# 04_Switch.net
KiCad netlist of a schematic drawn in Altium Designer
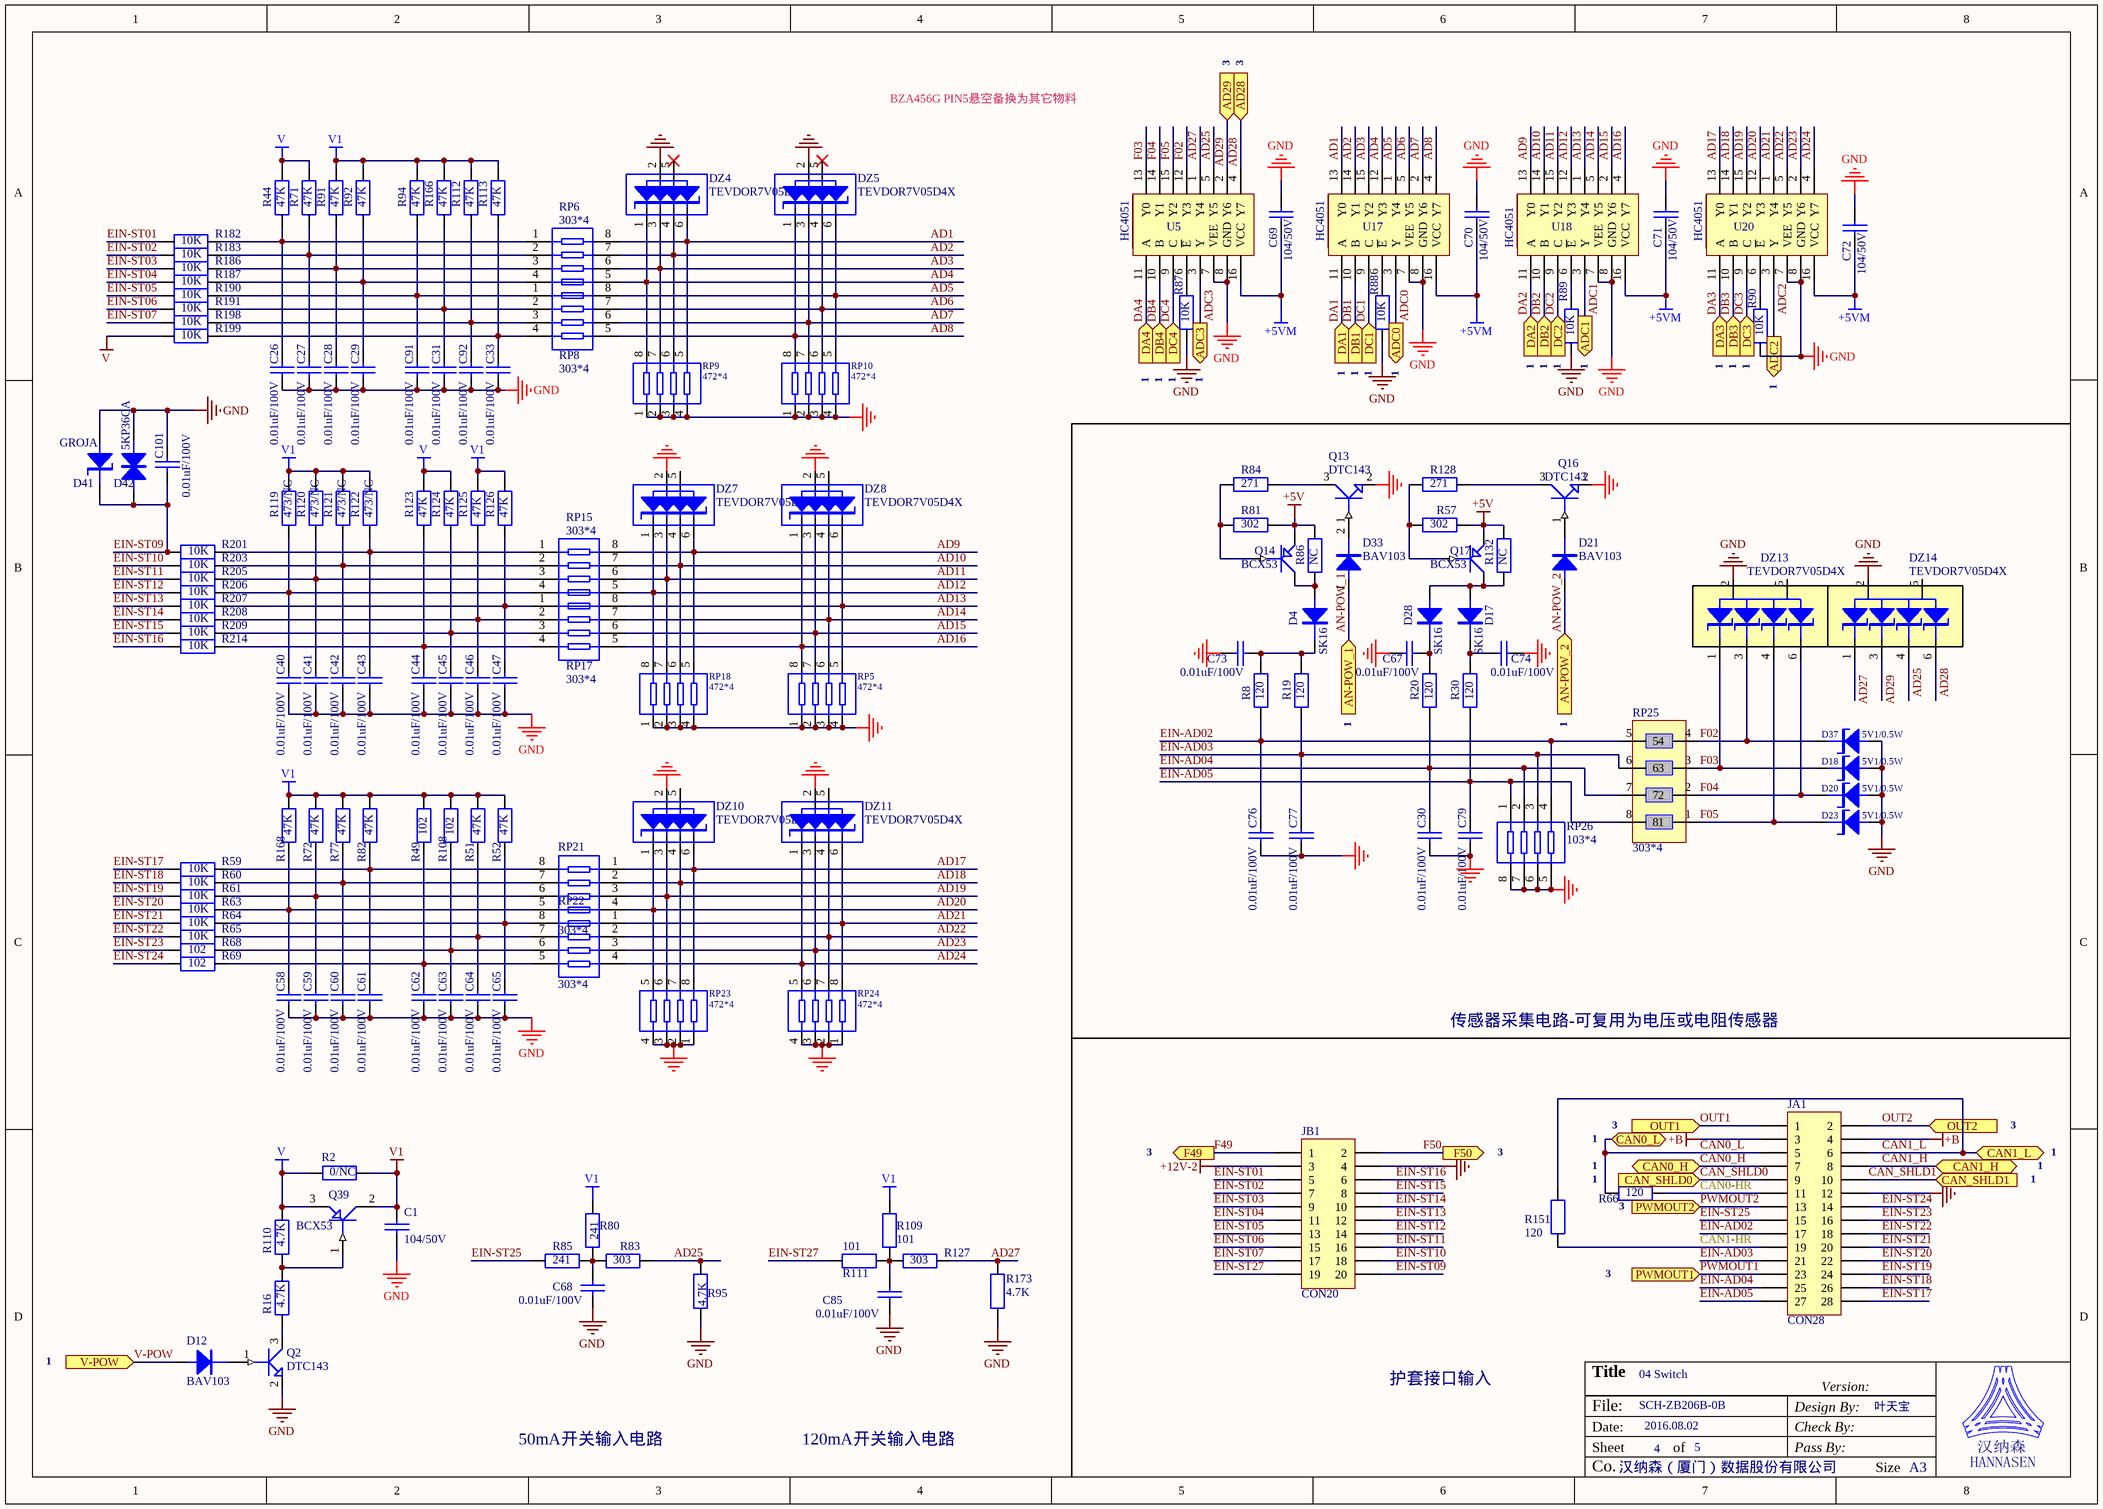
[diagram p0: 04 Switch.SchDoc]

(export (version "E")
  (design (tool "Eeschema 10.0.6"))
  (components
    (comp (ref "C1")
      (value "104/50V")
      (footprint "CR0805")
      (description "贴片电容")
      (libsource (lib "*") (part "CAP"))
    )
    (comp (ref "C26")
      (value "0.01uF/100V")
      (footprint "CR0805")
      (description "Capacitor")
      (libsource (lib "*") (part "CAP"))
    )
    (comp (ref "C27")
      (value "0.01uF/100V")
      (footprint "CR0805")
      (description "Capacitor")
      (libsource (lib "*") (part "CAP"))
    )
    (comp (ref "C28")
      (value "0.01uF/100V")
      (footprint "CR0805")
      (description "Capacitor")
      (libsource (lib "*") (part "CAP"))
    )
    (comp (ref "C29")
      (value "0.01uF/100V")
      (footprint "CR0805")
      (description "Capacitor")
      (libsource (lib "*") (part "CAP"))
    )
    (comp (ref "C30")
      (value "0.01uF/100V")
      (footprint "CR0805")
      (description "Capacitor")
      (libsource (lib "*") (part "CAP"))
    )
    (comp (ref "C31")
      (value "0.01uF/100V")
      (footprint "CR0805")
      (description "Capacitor")
      (libsource (lib "*") (part "CAP"))
    )
    (comp (ref "C33")
      (value "0.01uF/100V")
      (footprint "CR0805")
      (description "Capacitor")
      (libsource (lib "*") (part "CAP"))
    )
    (comp (ref "C40")
      (value "0.01uF/100V")
      (footprint "CR0805")
      (description "Capacitor")
      (libsource (lib "*") (part "CAP"))
    )
    (comp (ref "C41")
      (value "0.01uF/100V")
      (footprint "CR0805")
      (description "Capacitor")
      (libsource (lib "*") (part "CAP"))
    )
    (comp (ref "C42")
      (value "0.01uF/100V")
      (footprint "CR0805")
      (description "Capacitor")
      (libsource (lib "*") (part "CAP"))
    )
    (comp (ref "C43")
      (value "0.01uF/100V")
      (footprint "CR0805")
      (description "Capacitor")
      (libsource (lib "*") (part "CAP"))
    )
    (comp (ref "C44")
      (value "0.01uF/100V")
      (footprint "CR0805")
      (description "Capacitor")
      (libsource (lib "*") (part "CAP"))
    )
    (comp (ref "C45")
      (value "0.01uF/100V")
      (footprint "CR0805")
      (description "Capacitor")
      (libsource (lib "*") (part "CAP"))
    )
    (comp (ref "C46")
      (value "0.01uF/100V")
      (footprint "CR0805")
      (description "Capacitor")
      (libsource (lib "*") (part "CAP"))
    )
    (comp (ref "C47")
      (value "0.01uF/100V")
      (footprint "CR0805")
      (description "Capacitor")
      (libsource (lib "*") (part "CAP"))
    )
    (comp (ref "C58")
      (value "0.01uF/100V")
      (footprint "CR0805")
      (description "Capacitor")
      (libsource (lib "*") (part "CAP"))
    )
    (comp (ref "C59")
      (value "0.01uF/100V")
      (footprint "CR0805")
      (description "Capacitor")
      (libsource (lib "*") (part "CAP"))
    )
    (comp (ref "C60")
      (value "0.01uF/100V")
      (footprint "CR0805")
      (description "Capacitor")
      (libsource (lib "*") (part "CAP"))
    )
    (comp (ref "C61")
      (value "0.01uF/100V")
      (footprint "CR0805")
      (description "Capacitor")
      (libsource (lib "*") (part "CAP"))
    )
    (comp (ref "C62")
      (value "0.01uF/100V")
      (footprint "CR0805")
      (description "Capacitor")
      (libsource (lib "*") (part "CAP"))
    )
    (comp (ref "C63")
      (value "0.01uF/100V")
      (footprint "CR0805")
      (description "Capacitor")
      (libsource (lib "*") (part "CAP"))
    )
    (comp (ref "C64")
      (value "0.01uF/100V")
      (footprint "CR0805")
      (description "Capacitor")
      (libsource (lib "*") (part "CAP"))
    )
    (comp (ref "C65")
      (value "0.01uF/100V")
      (footprint "CR0805")
      (description "Capacitor")
      (libsource (lib "*") (part "CAP"))
    )
    (comp (ref "C67")
      (value "0.01uF/100V")
      (footprint "CR0805")
      (description "Capacitor")
      (libsource (lib "*") (part "CAP"))
    )
    (comp (ref "C68")
      (value "0.01uF/100V")
      (footprint "CR0805")
      (description "Capacitor")
      (libsource (lib "*") (part "CAP"))
    )
    (comp (ref "C69")
      (value "104/50V")
      (footprint "CR0805")
      (description "Capacitor")
      (libsource (lib "*") (part "CAP"))
    )
    (comp (ref "C70")
      (value "104/50V")
      (footprint "CR0805")
      (description "Capacitor")
      (libsource (lib "*") (part "CAP"))
    )
    (comp (ref "C71")
      (value "104/50V")
      (footprint "CR0805")
      (description "Capacitor")
      (libsource (lib "*") (part "CAP"))
    )
    (comp (ref "C72")
      (value "104/50V")
      (footprint "CR0805")
      (description "Capacitor")
      (libsource (lib "*") (part "CAP"))
    )
    (comp (ref "C73")
      (value "0.01uF/100V")
      (footprint "CR0805")
      (description "Capacitor")
      (libsource (lib "*") (part "CAP"))
    )
    (comp (ref "C74")
      (value "0.01uF/100V")
      (footprint "CR0805")
      (description "Capacitor")
      (libsource (lib "*") (part "CAP"))
    )
    (comp (ref "C76")
      (value "0.01uF/100V")
      (footprint "CR0805")
      (description "Capacitor")
      (libsource (lib "*") (part "CAP"))
    )
    (comp (ref "C77")
      (value "0.01uF/100V")
      (footprint "CR0805")
      (description "Capacitor")
      (libsource (lib "*") (part "CAP"))
    )
    (comp (ref "C79")
      (value "0.01uF/100V")
      (footprint "CR0805")
      (description "Capacitor")
      (libsource (lib "*") (part "CAP"))
    )
    (comp (ref "C85")
      (value "0.01uF/100V")
      (footprint "CR0805")
      (description "Capacitor")
      (libsource (lib "*") (part "CAP"))
    )
    (comp (ref "C91")
      (value "0.01uF/100V")
      (footprint "CR0805")
      (description "Capacitor")
      (libsource (lib "*") (part "CAP"))
    )
    (comp (ref "C92")
      (value "0.01uF/100V")
      (footprint "CR0805")
      (description "Capacitor")
      (libsource (lib "*") (part "CAP"))
    )
    (comp (ref "C101")
      (value "0.01uF/100V")
      (footprint "CR0805")
      (description "Capacitor")
      (libsource (lib "*") (part "CAP"))
    )
    (comp (ref "D4")
      (value "SK16")
      (footprint "SMA")
      (description "二极管")
      (libsource (lib "*") (part "DIODE"))
    )
    (comp (ref "D12")
      (value "BAV103")
      (footprint "SOD-80C")
      (description "二极管")
      (libsource (lib "*") (part "DIODE"))
    )
    (comp (ref "D17")
      (value "SK16")
      (footprint "SMA")
      (description "二极管")
      (libsource (lib "*") (part "DIODE"))
    )
    (comp (ref "D18")
      (value "5V1/0.5W")
      (footprint "SOD-80C")
      (description "稳压二极管")
      (libsource (lib "*") (part "DW"))
    )
    (comp (ref "D20")
      (value "5V1/0.5W")
      (footprint "SOD-80C")
      (description "稳压二极管")
      (libsource (lib "*") (part "DW"))
    )
    (comp (ref "D21")
      (value "BAV103")
      (footprint "SOD-80C")
      (description "二极管")
      (libsource (lib "*") (part "DIODE"))
    )
    (comp (ref "D23")
      (value "5V1/0.5W")
      (footprint "SOD-80C")
      (description "稳压二极管")
      (libsource (lib "*") (part "DW"))
    )
    (comp (ref "D28")
      (value "SK16")
      (footprint "SMA")
      (description "二极管")
      (libsource (lib "*") (part "DIODE"))
    )
    (comp (ref "D33")
      (value "BAV103")
      (footprint "SOD-80C")
      (description "二极管")
      (libsource (lib "") (part "DIODE_1"))
    )
    (comp (ref "D37")
      (value "5V1/0.5W")
      (footprint "SOD-80C")
      (description "稳压二极管")
      (libsource (lib "*") (part "DW"))
    )
    (comp (ref "D41")
      (value "GROJA")
      (footprint "SMA")
      (description "稳压二极管")
      (libsource (lib "*") (part "DW"))
    )
    (comp (ref "D42") (value "5KP36CA") (footprint "SMB-D") (libsource (lib "*") (part "TVS")))
    (comp (ref "DZ4")
      (value "TEVDOR7V05D4X")
      (footprint "SOT-457")
      (description "二极管排")
      (libsource (lib "yibiaoschlib") (part "TEVDOR7V05D4X"))
    )
    (comp (ref "DZ5")
      (value "TEVDOR7V05D4X")
      (footprint "SOT-457")
      (description "二极管排")
      (libsource (lib "yibiaoschlib") (part "TEVDOR7V05D4X"))
    )
    (comp (ref "DZ7")
      (value "TEVDOR7V05D4X")
      (footprint "SOT-457")
      (description "二极管排")
      (libsource (lib "yibiaoschlib") (part "TEVDOR7V05D4X"))
    )
    (comp (ref "DZ8")
      (value "TEVDOR7V05D4X")
      (footprint "SOT-457")
      (description "二极管排")
      (libsource (lib "yibiaoschlib") (part "TEVDOR7V05D4X"))
    )
    (comp (ref "DZ10")
      (value "TEVDOR7V05D4X")
      (footprint "SOT-457")
      (description "二极管排")
      (libsource (lib "yibiaoschlib") (part "TEVDOR7V05D4X"))
    )
    (comp (ref "DZ11")
      (value "TEVDOR7V05D4X")
      (footprint "SOT-457")
      (description "二极管排")
      (libsource (lib "yibiaoschlib") (part "TEVDOR7V05D4X"))
    )
    (comp (ref "DZ13")
      (value "TEVDOR7V05D4X")
      (footprint "SOT-457")
      (description "二极管排")
      (libsource (lib "*") (part "TEVDOR7V05D4X"))
    )
    (comp (ref "DZ14")
      (value "TEVDOR7V05D4X")
      (footprint "SOT-457")
      (description "二极管排")
      (libsource (lib "*") (part "TEVDOR7V05D4X"))
    )
    (comp (ref "JA1") (value "CON28") (footprint "AMP DIP28") (libsource (lib "YDM-SQ-1SCH") (part "CON28")))
    (comp (ref "JB1") (value "CON20") (footprint "AMP DIP20") (libsource (lib "YDM-SQ-1SCH") (part "CON20")))
    (comp (ref "Q2")
      (value "DTC143")
      (footprint "SOT23")
      (description "NPN")
      (libsource (lib "Ô­ÀíÍ¼¿â-1SCH") (part "DTC143"))
    )
    (comp (ref "Q13")
      (value "DTC143")
      (footprint "SOT23")
      (description "NPN")
      (libsource (lib "Ô­ÀíÍ¼¿â-1SCH") (part "DTC143"))
    )
    (comp (ref "Q14")
      (value "BCX53")
      (footprint "SOT89")
      (description "贴片三极管")
      (libsource (lib "*") (part "PNP1"))
    )
    (comp (ref "Q16")
      (value "DTC143")
      (footprint "SOT23")
      (description "NPN")
      (libsource (lib "Ô­ÀíÍ¼¿â-1SCH") (part "DTC143"))
    )
    (comp (ref "Q17")
      (value "BCX53")
      (footprint "SOT89")
      (description "贴片三极管")
      (libsource (lib "*") (part "PNP1"))
    )
    (comp (ref "Q39")
      (value "BCX53")
      (footprint "SOT89")
      (description "PNP三极管")
      (libsource (lib "Ô­ÀíÍ¼¿â-1SCH") (part "BSP631"))
    )
    (comp (ref "R2")
      (value "0/NC")
      (footprint "CR1206")
      (description "贴片电阻")
      (libsource (lib "YDM-SQ-1SCH") (part "RES"))
    )
    (comp (ref "R8")
      (value "120")
      (footprint "CR1206")
      (description "贴片电阻")
      (libsource (lib "*") (part "RES"))
    )
    (comp (ref "R16")
      (value "4.7K")
      (footprint "CR1206")
      (description "贴片电阻")
      (libsource (lib "*") (part "RES"))
    )
    (comp (ref "R19")
      (value "120")
      (footprint "CR1206")
      (description "贴片电阻")
      (libsource (lib "*") (part "RES"))
    )
    (comp (ref "R20")
      (value "120")
      (footprint "CR1206")
      (description "贴片电阻")
      (libsource (lib "*") (part "RES"))
    )
    (comp (ref "R30")
      (value "120")
      (footprint "CR1206")
      (description "贴片电阻")
      (libsource (lib "*") (part "RES"))
    )
    (comp (ref "R44")
      (value "47K")
      (footprint "CR0805")
      (description "贴片电阻")
      (libsource (lib "*") (part "RES"))
    )
    (comp (ref "R49")
      (value "102")
      (footprint "CR2010")
      (description "贴片电阻")
      (libsource (lib "*") (part "RES"))
    )
    (comp (ref "R51")
      (value "47K")
      (footprint "CR0805")
      (description "贴片电阻")
      (libsource (lib "*") (part "RES"))
    )
    (comp (ref "R52")
      (value "47K")
      (footprint "CR0805")
      (description "贴片电阻")
      (libsource (lib "*") (part "RES"))
    )
    (comp (ref "R57")
      (value "302")
      (footprint "CR0805")
      (description "贴片电阻")
      (libsource (lib "*") (part "RES"))
    )
    (comp (ref "R59")
      (value "10K")
      (footprint "CR1206")
      (description "贴片电阻")
      (libsource (lib "*") (part "RES"))
    )
    (comp (ref "R60")
      (value "10K")
      (footprint "CR1206")
      (description "贴片电阻")
      (libsource (lib "*") (part "RES"))
    )
    (comp (ref "R61")
      (value "10K")
      (footprint "CR1206")
      (description "贴片电阻")
      (libsource (lib "*") (part "RES"))
    )
    (comp (ref "R63")
      (value "10K")
      (footprint "CR1206")
      (description "贴片电阻")
      (libsource (lib "*") (part "RES"))
    )
    (comp (ref "R64")
      (value "10K")
      (footprint "CR1206")
      (description "贴片电阻")
      (libsource (lib "*") (part "RES"))
    )
    (comp (ref "R65")
      (value "10K")
      (footprint "CR1206")
      (description "贴片电阻")
      (libsource (lib "*") (part "RES"))
    )
    (comp (ref "R66")
      (value "120")
      (footprint "CR0805")
      (description "贴片电阻")
      (libsource (lib "*") (part "RES"))
    )
    (comp (ref "R68")
      (value "102")
      (footprint "CR2010")
      (description "贴片电阻")
      (libsource (lib "*") (part "RES"))
    )
    (comp (ref "R69")
      (value "102")
      (footprint "CR2010")
      (description "贴片电阻")
      (libsource (lib "*") (part "RES"))
    )
    (comp (ref "R71")
      (value "47K")
      (footprint "CR0805")
      (description "贴片电阻")
      (libsource (lib "*") (part "RES"))
    )
    (comp (ref "R72")
      (value "47K")
      (footprint "CR0805")
      (description "贴片电阻")
      (libsource (lib "*") (part "RES"))
    )
    (comp (ref "R77")
      (value "47K")
      (footprint "CR0805")
      (description "贴片电阻")
      (libsource (lib "*") (part "RES"))
    )
    (comp (ref "R80")
      (value "241")
      (footprint "R-3W")
      (description "贴片电阻")
      (libsource (lib "*") (part "RES"))
    )
    (comp (ref "R81")
      (value "302")
      (footprint "CR0805")
      (description "贴片电阻")
      (libsource (lib "*") (part "RES"))
    )
    (comp (ref "R82")
      (value "47K")
      (footprint "CR0805")
      (description "贴片电阻")
      (libsource (lib "*") (part "RES"))
    )
    (comp (ref "R83")
      (value "303")
      (footprint "CR0805")
      (description "贴片电阻")
      (libsource (lib "*") (part "RES"))
    )
    (comp (ref "R84")
      (value "271")
      (footprint "CR0805")
      (description "贴片电阻")
      (libsource (lib "*") (part "RES"))
    )
    (comp (ref "R85")
      (value "241")
      (footprint "R-3W")
      (description "贴片电阻")
      (libsource (lib "*") (part "RES"))
    )
    (comp (ref "R86")
      (value "NC")
      (footprint "CR1206")
      (description "贴片电阻")
      (libsource (lib "*") (part "RES"))
    )
    (comp (ref "R87")
      (value "10K")
      (footprint "CR0805")
      (description "贴片电阻")
      (libsource (lib "*") (part "RES"))
    )
    (comp (ref "R88")
      (value "10K")
      (footprint "CR0805")
      (description "贴片电阻")
      (libsource (lib "*") (part "RES"))
    )
    (comp (ref "R89")
      (value "10K")
      (footprint "CR0805")
      (description "贴片电阻")
      (libsource (lib "*") (part "RES"))
    )
    (comp (ref "R90")
      (value "10K")
      (footprint "CR0805")
      (description "贴片电阻")
      (libsource (lib "*") (part "RES"))
    )
    (comp (ref "R91")
      (value "47K")
      (footprint "CR0805")
      (description "贴片电阻")
      (libsource (lib "*") (part "RES"))
    )
    (comp (ref "R92")
      (value "47K")
      (footprint "CR0805")
      (description "贴片电阻")
      (libsource (lib "*") (part "RES"))
    )
    (comp (ref "R94")
      (value "47K")
      (footprint "CR0805")
      (description "贴片电阻")
      (libsource (lib "*") (part "RES"))
    )
    (comp (ref "R95")
      (value "4.7K")
      (footprint "CR0805")
      (description "贴片电阻")
      (libsource (lib "*") (part "RES"))
    )
    (comp (ref "R108")
      (value "102")
      (footprint "CR2010")
      (description "贴片电阻")
      (libsource (lib "*") (part "RES"))
    )
    (comp (ref "R109")
      (value "101")
      (footprint "R-3W")
      (description "贴片电阻")
      (libsource (lib "*") (part "RES"))
    )
    (comp (ref "R110")
      (value "4.7K")
      (footprint "CR0805")
      (description "贴片电阻")
      (libsource (lib "*") (part "RES"))
    )
    (comp (ref "R111")
      (value "101")
      (footprint "R-3W")
      (description "贴片电阻")
      (libsource (lib "*") (part "RES"))
    )
    (comp (ref "R112")
      (value "47K")
      (footprint "CR0805")
      (description "贴片电阻")
      (libsource (lib "*") (part "RES"))
    )
    (comp (ref "R113")
      (value "47K")
      (footprint "CR0805")
      (description "贴片电阻")
      (libsource (lib "*") (part "RES"))
    )
    (comp (ref "R119")
      (value "473/NC")
      (footprint "CR0805")
      (description "贴片电阻")
      (libsource (lib "*") (part "RES"))
    )
    (comp (ref "R120")
      (value "473/NC")
      (footprint "CR0805")
      (description "贴片电阻")
      (libsource (lib "*") (part "RES"))
    )
    (comp (ref "R121")
      (value "473/NC")
      (footprint "CR0805")
      (description "贴片电阻")
      (libsource (lib "*") (part "RES"))
    )
    (comp (ref "R122")
      (value "473/NC")
      (footprint "CR0805")
      (description "贴片电阻")
      (libsource (lib "*") (part "RES"))
    )
    (comp (ref "R123")
      (value "47K")
      (footprint "CR0805")
      (description "贴片电阻")
      (libsource (lib "*") (part "RES"))
    )
    (comp (ref "R124")
      (value "47K")
      (footprint "CR0805")
      (description "贴片电阻")
      (libsource (lib "*") (part "RES"))
    )
    (comp (ref "R125")
      (value "47K")
      (footprint "CR0805")
      (description "贴片电阻")
      (libsource (lib "*") (part "RES"))
    )
    (comp (ref "R126")
      (value "47K")
      (footprint "CR0805")
      (description "贴片电阻")
      (libsource (lib "*") (part "RES"))
    )
    (comp (ref "R127")
      (value "303")
      (footprint "CR0805")
      (description "贴片电阻")
      (libsource (lib "*") (part "RES"))
    )
    (comp (ref "R128")
      (value "271")
      (footprint "CR0805")
      (description "贴片电阻")
      (libsource (lib "*") (part "RES"))
    )
    (comp (ref "R132")
      (value "NC")
      (footprint "CR1206")
      (description "贴片电阻")
      (libsource (lib "*") (part "RES"))
    )
    (comp (ref "R151")
      (value "120")
      (footprint "CR0805")
      (description "贴片电阻")
      (libsource (lib "*") (part "RES"))
    )
    (comp (ref "R166")
      (value "47K")
      (footprint "CR0805")
      (description "贴片电阻")
      (libsource (lib "*") (part "RES"))
    )
    (comp (ref "R168")
      (value "47K")
      (footprint "CR0805")
      (description "贴片电阻")
      (libsource (lib "*") (part "RES"))
    )
    (comp (ref "R173")
      (value "4.7K")
      (footprint "CR0805")
      (description "贴片电阻")
      (libsource (lib "*") (part "RES"))
    )
    (comp (ref "R182")
      (value "10K")
      (footprint "CR1206")
      (description "贴片电阻")
      (libsource (lib "*") (part "RES"))
    )
    (comp (ref "R183")
      (value "10K")
      (footprint "CR1206")
      (description "贴片电阻")
      (libsource (lib "*") (part "RES"))
    )
    (comp (ref "R186")
      (value "10K")
      (footprint "CR1206")
      (description "贴片电阻")
      (libsource (lib "*") (part "RES"))
    )
    (comp (ref "R187")
      (value "10K")
      (footprint "CR1206")
      (description "贴片电阻")
      (libsource (lib "*") (part "RES"))
    )
    (comp (ref "R190")
      (value "10K")
      (footprint "CR1206")
      (description "贴片电阻")
      (libsource (lib "*") (part "RES"))
    )
    (comp (ref "R191")
      (value "10K")
      (footprint "CR1206")
      (description "贴片电阻")
      (libsource (lib "*") (part "RES"))
    )
    (comp (ref "R198")
      (value "10K")
      (footprint "CR1206")
      (description "贴片电阻")
      (libsource (lib "*") (part "RES"))
    )
    (comp (ref "R199")
      (value "10K")
      (footprint "CR1206")
      (description "贴片电阻")
      (libsource (lib "*") (part "RES"))
    )
    (comp (ref "R201")
      (value "10K")
      (footprint "CR1206")
      (description "贴片电阻")
      (libsource (lib "*") (part "RES"))
    )
    (comp (ref "R203")
      (value "10K")
      (footprint "CR1206")
      (description "贴片电阻")
      (libsource (lib "*") (part "RES"))
    )
    (comp (ref "R205")
      (value "10K")
      (footprint "CR1206")
      (description "贴片电阻")
      (libsource (lib "*") (part "RES"))
    )
    (comp (ref "R206")
      (value "10K")
      (footprint "CR1206")
      (description "贴片电阻")
      (libsource (lib "*") (part "RES"))
    )
    (comp (ref "R207")
      (value "10K")
      (footprint "CR1206")
      (description "贴片电阻")
      (libsource (lib "*") (part "RES"))
    )
    (comp (ref "R208")
      (value "10K")
      (footprint "CR1206")
      (description "贴片电阻")
      (libsource (lib "*") (part "RES"))
    )
    (comp (ref "R209")
      (value "10K")
      (footprint "CR1206")
      (description "贴片电阻")
      (libsource (lib "*") (part "RES"))
    )
    (comp (ref "R214")
      (value "10K")
      (footprint "CR1206")
      (description "贴片电阻")
      (libsource (lib "*") (part "RES"))
    )
    (comp (ref "RP5")
      (value "472*4")
      (footprint "R4")
      (description "排阻")
      (libsource (lib "yibiaoschlib") (part "RN"))
    )
    (comp (ref "RP6")
      (value "303*4")
      (footprint "R4")
      (description "贴片排阻")
      (libsource (lib "*") (part "R_LINE4"))
    )
    (comp (ref "RP8")
      (value "303*4")
      (footprint "R4")
      (description "贴片排阻")
      (libsource (lib "*") (part "R_LINE4"))
    )
    (comp (ref "RP9")
      (value "472*4")
      (footprint "R4")
      (description "排阻")
      (libsource (lib "yibiaoschlib") (part "RN"))
    )
    (comp (ref "RP10")
      (value "472*4")
      (footprint "R4")
      (description "排阻")
      (libsource (lib "yibiaoschlib") (part "RN"))
    )
    (comp (ref "RP15")
      (value "303*4")
      (footprint "R4")
      (description "贴片排阻")
      (libsource (lib "*") (part "R_LINE4"))
    )
    (comp (ref "RP17")
      (value "303*4")
      (footprint "R4")
      (description "贴片排阻")
      (libsource (lib "*") (part "R_LINE4"))
    )
    (comp (ref "RP18")
      (value "472*4")
      (footprint "R4")
      (description "排阻")
      (libsource (lib "yibiaoschlib") (part "RN"))
    )
    (comp (ref "RP21")
      (value "303*4")
      (footprint "R4")
      (description "贴片排阻")
      (libsource (lib "*") (part "R_LINE4"))
    )
    (comp (ref "RP22")
      (value "303*4")
      (footprint "R4")
      (description "贴片排阻")
      (libsource (lib "*") (part "R_LINE4"))
    )
    (comp (ref "RP23")
      (value "472*4")
      (footprint "R4")
      (description "排阻")
      (libsource (lib "yibiaoschlib") (part "RN"))
    )
    (comp (ref "RP24")
      (value "472*4")
      (footprint "R4")
      (description "排阻")
      (libsource (lib "yibiaoschlib") (part "RN"))
    )
    (comp (ref "RP25") (value "303*4") (footprint "R4") (libsource (lib "*") (part "R_ARRAY")))
    (comp (ref "RP26")
      (value "103*4")
      (footprint "R4")
      (description "排阻")
      (libsource (lib "*") (part "R_LINE4"))
    )
    (comp (ref "U5")
      (value "HC4051")
      (footprint "SO-16")
      (description "IC-8路模拟开关集成快")
      (libsource (lib "YDM-SQ-1SCH") (part "HC4051"))
    )
    (comp (ref "U17")
      (value "HC4051")
      (footprint "SO-16")
      (description "IC-8路模拟开关集成快")
      (libsource (lib "YDM-SQ-1SCH") (part "HC4051"))
    )
    (comp (ref "U18")
      (value "HC4051")
      (footprint "SO-16")
      (description "IC-8路模拟开关集成快")
      (libsource (lib "YDM-SQ-1SCH") (part "HC4051"))
    )
    (comp (ref "U20")
      (value "HC4051")
      (footprint "SO-16")
      (description "IC-8路模拟开关集成快")
      (libsource (lib "YDM-SQ-1SCH") (part "HC4051"))
    )
  )
  (nets
    (net (code "1") (name "+5V") (class "Default")
      (node (ref "Q14") (pin "3") (pinfunction "E_3") (pintype "passive"))
      (node (ref "Q17") (pin "3") (pinfunction "E_3") (pintype "passive"))
      (node (ref "R132") (pin "1") (pinfunction "1_1") (pintype "passive"))
      (node (ref "R57") (pin "1") (pinfunction "1_1") (pintype "passive"))
      (node (ref "R81") (pin "1") (pinfunction "1_1") (pintype "passive"))
      (node (ref "R86") (pin "1") (pinfunction "1_1") (pintype "passive"))
    )
    (net (code "2") (name "+5VM") (class "Default")
      (node (ref "C69") (pin "2") (pinfunction "2_2") (pintype "passive"))
      (node (ref "C70") (pin "2") (pinfunction "2_2") (pintype "passive"))
      (node (ref "C71") (pin "2") (pinfunction "2_2") (pintype "passive"))
      (node (ref "C72") (pin "2") (pinfunction "2_2") (pintype "passive"))
      (node (ref "U17") (pin "16") (pinfunction "VCC_16") (pintype "passive"))
      (node (ref "U18") (pin "16") (pinfunction "VCC_16") (pintype "passive"))
      (node (ref "U20") (pin "16") (pinfunction "VCC_16") (pintype "passive"))
      (node (ref "U5") (pin "16") (pinfunction "VCC_16") (pintype "passive"))
    )
    (net (code "3") (name "+12V-2") (class "Default")
      (node (ref "JB1") (pin "3") (pinfunction "3_3") (pintype "passive"))
    )
    (net (code "4") (name "+B") (class "Default")
      (node (ref "JA1") (pin "3") (pinfunction "3_3") (pintype "passive"))
      (node (ref "JA1") (pin "4") (pinfunction "4_4") (pintype "passive"))
    )
    (net (code "5") (name "/AD1") (class "Default")
      (node (ref "DZ4") (pin "6") (pintype "passive"))
      (node (ref "RP6") (pin "8") (pinfunction "8_8") (pintype "passive"))
      (node (ref "RP9") (pin "5") (pinfunction "5_5") (pintype "passive"))
      (node (ref "U17") (pin "13") (pinfunction "Y0_13") (pintype "passive"))
    )
    (net (code "6") (name "/AD2") (class "Default")
      (node (ref "DZ4") (pin "4") (pintype "passive"))
      (node (ref "RP6") (pin "7") (pinfunction "7_7") (pintype "passive"))
      (node (ref "RP9") (pin "6") (pinfunction "6_6") (pintype "passive"))
      (node (ref "U17") (pin "14") (pinfunction "Y1_14") (pintype "passive"))
    )
    (net (code "7") (name "/AD3") (class "Default")
      (node (ref "DZ4") (pin "3") (pintype "passive"))
      (node (ref "RP6") (pin "6") (pinfunction "6_6") (pintype "passive"))
      (node (ref "RP9") (pin "7") (pinfunction "7_7") (pintype "passive"))
      (node (ref "U17") (pin "15") (pinfunction "Y2_15") (pintype "passive"))
    )
    (net (code "8") (name "/AD4") (class "Default")
      (node (ref "DZ4") (pin "1") (pintype "passive"))
      (node (ref "RP6") (pin "5") (pinfunction "5_5") (pintype "passive"))
      (node (ref "RP9") (pin "8") (pinfunction "8_8") (pintype "passive"))
      (node (ref "U17") (pin "12") (pinfunction "Y3_12") (pintype "passive"))
    )
    (net (code "9") (name "/AD5") (class "Default")
      (node (ref "DZ5") (pin "6") (pintype "passive"))
      (node (ref "RP10") (pin "5") (pinfunction "5_5") (pintype "passive"))
      (node (ref "RP8") (pin "8") (pinfunction "8_8") (pintype "passive"))
      (node (ref "U17") (pin "1") (pinfunction "Y4_1") (pintype "passive"))
    )
    (net (code "10") (name "/AD6") (class "Default")
      (node (ref "DZ5") (pin "4") (pintype "passive"))
      (node (ref "RP10") (pin "6") (pinfunction "6_6") (pintype "passive"))
      (node (ref "RP8") (pin "7") (pinfunction "7_7") (pintype "passive"))
      (node (ref "U17") (pin "5") (pinfunction "Y5_5") (pintype "passive"))
    )
    (net (code "11") (name "/AD7") (class "Default")
      (node (ref "DZ5") (pin "3") (pintype "passive"))
      (node (ref "RP10") (pin "7") (pinfunction "7_7") (pintype "passive"))
      (node (ref "RP8") (pin "6") (pinfunction "6_6") (pintype "passive"))
      (node (ref "U17") (pin "2") (pinfunction "Y6_2") (pintype "passive"))
    )
    (net (code "12") (name "/AD8") (class "Default")
      (node (ref "DZ5") (pin "1") (pintype "passive"))
      (node (ref "RP10") (pin "8") (pinfunction "8_8") (pintype "passive"))
      (node (ref "RP8") (pin "5") (pinfunction "5_5") (pintype "passive"))
      (node (ref "U17") (pin "4") (pinfunction "Y7_4") (pintype "passive"))
    )
    (net (code "13") (name "/AD9") (class "Default")
      (node (ref "DZ7") (pin "6") (pintype "passive"))
      (node (ref "RP15") (pin "8") (pinfunction "8_8") (pintype "passive"))
      (node (ref "RP18") (pin "5") (pinfunction "5_5") (pintype "passive"))
      (node (ref "U18") (pin "13") (pinfunction "Y0_13") (pintype "passive"))
    )
    (net (code "14") (name "/AD10") (class "Default")
      (node (ref "DZ7") (pin "4") (pintype "passive"))
      (node (ref "RP15") (pin "7") (pinfunction "7_7") (pintype "passive"))
      (node (ref "RP18") (pin "6") (pinfunction "6_6") (pintype "passive"))
      (node (ref "U18") (pin "14") (pinfunction "Y1_14") (pintype "passive"))
    )
    (net (code "15") (name "/AD11") (class "Default")
      (node (ref "DZ7") (pin "3") (pintype "passive"))
      (node (ref "RP15") (pin "6") (pinfunction "6_6") (pintype "passive"))
      (node (ref "RP18") (pin "7") (pinfunction "7_7") (pintype "passive"))
      (node (ref "U18") (pin "15") (pinfunction "Y2_15") (pintype "passive"))
    )
    (net (code "16") (name "/AD12") (class "Default")
      (node (ref "DZ7") (pin "1") (pintype "passive"))
      (node (ref "RP15") (pin "5") (pinfunction "5_5") (pintype "passive"))
      (node (ref "RP18") (pin "8") (pinfunction "8_8") (pintype "passive"))
      (node (ref "U18") (pin "12") (pinfunction "Y3_12") (pintype "passive"))
    )
    (net (code "17") (name "/AD13") (class "Default")
      (node (ref "DZ8") (pin "6") (pintype "passive"))
      (node (ref "RP17") (pin "8") (pinfunction "8_8") (pintype "passive"))
      (node (ref "RP5") (pin "5") (pinfunction "5_5") (pintype "passive"))
      (node (ref "U18") (pin "1") (pinfunction "Y4_1") (pintype "passive"))
    )
    (net (code "18") (name "/AD14") (class "Default")
      (node (ref "DZ8") (pin "4") (pintype "passive"))
      (node (ref "RP17") (pin "7") (pinfunction "7_7") (pintype "passive"))
      (node (ref "RP5") (pin "6") (pinfunction "6_6") (pintype "passive"))
      (node (ref "U18") (pin "5") (pinfunction "Y5_5") (pintype "passive"))
    )
    (net (code "19") (name "/AD15") (class "Default")
      (node (ref "DZ8") (pin "3") (pintype "passive"))
      (node (ref "RP17") (pin "6") (pinfunction "6_6") (pintype "passive"))
      (node (ref "RP5") (pin "7") (pinfunction "7_7") (pintype "passive"))
      (node (ref "U18") (pin "2") (pinfunction "Y6_2") (pintype "passive"))
    )
    (net (code "20") (name "/AD16") (class "Default")
      (node (ref "DZ8") (pin "1") (pintype "passive"))
      (node (ref "RP17") (pin "5") (pinfunction "5_5") (pintype "passive"))
      (node (ref "RP5") (pin "8") (pinfunction "8_8") (pintype "passive"))
      (node (ref "U18") (pin "4") (pinfunction "Y7_4") (pintype "passive"))
    )
    (net (code "21") (name "/AD17") (class "Default")
      (node (ref "DZ10") (pin "6") (pintype "passive"))
      (node (ref "RP21") (pin "1") (pinfunction "1_1") (pintype "passive"))
      (node (ref "RP23") (pin "8") (pinfunction "8_8") (pintype "passive"))
      (node (ref "U20") (pin "13") (pinfunction "Y0_13") (pintype "passive"))
    )
    (net (code "22") (name "/AD18") (class "Default")
      (node (ref "DZ10") (pin "4") (pintype "passive"))
      (node (ref "RP21") (pin "2") (pinfunction "2_2") (pintype "passive"))
      (node (ref "RP23") (pin "7") (pinfunction "7_7") (pintype "passive"))
      (node (ref "U20") (pin "14") (pinfunction "Y1_14") (pintype "passive"))
    )
    (net (code "23") (name "/AD19") (class "Default")
      (node (ref "DZ10") (pin "3") (pintype "passive"))
      (node (ref "RP21") (pin "3") (pinfunction "3_3") (pintype "passive"))
      (node (ref "RP23") (pin "6") (pinfunction "6_6") (pintype "passive"))
      (node (ref "U20") (pin "15") (pinfunction "Y2_15") (pintype "passive"))
    )
    (net (code "24") (name "/AD20") (class "Default")
      (node (ref "DZ10") (pin "1") (pintype "passive"))
      (node (ref "RP21") (pin "4") (pinfunction "4_4") (pintype "passive"))
      (node (ref "RP23") (pin "5") (pinfunction "5_5") (pintype "passive"))
      (node (ref "U20") (pin "12") (pinfunction "Y3_12") (pintype "passive"))
    )
    (net (code "25") (name "/AD21") (class "Default")
      (node (ref "DZ11") (pin "6") (pintype "passive"))
      (node (ref "RP22") (pin "1") (pinfunction "1_1") (pintype "passive"))
      (node (ref "RP24") (pin "8") (pinfunction "8_8") (pintype "passive"))
      (node (ref "U20") (pin "1") (pinfunction "Y4_1") (pintype "passive"))
    )
    (net (code "26") (name "/AD22") (class "Default")
      (node (ref "DZ11") (pin "4") (pintype "passive"))
      (node (ref "RP22") (pin "2") (pinfunction "2_2") (pintype "passive"))
      (node (ref "RP24") (pin "7") (pinfunction "7_7") (pintype "passive"))
      (node (ref "U20") (pin "5") (pinfunction "Y5_5") (pintype "passive"))
    )
    (net (code "27") (name "/AD23") (class "Default")
      (node (ref "DZ11") (pin "3") (pintype "passive"))
      (node (ref "RP22") (pin "3") (pinfunction "3_3") (pintype "passive"))
      (node (ref "RP24") (pin "6") (pinfunction "6_6") (pintype "passive"))
      (node (ref "U20") (pin "2") (pinfunction "Y6_2") (pintype "passive"))
    )
    (net (code "28") (name "/AD24") (class "Default")
      (node (ref "DZ11") (pin "1") (pintype "passive"))
      (node (ref "RP22") (pin "4") (pinfunction "4_4") (pintype "passive"))
      (node (ref "RP24") (pin "5") (pinfunction "5_5") (pintype "passive"))
      (node (ref "U20") (pin "4") (pinfunction "Y7_4") (pintype "passive"))
    )
    (net (code "29") (name "/AD25") (class "Default")
      (node (ref "DZ14") (pin "4") (pintype "passive"))
      (node (ref "R83") (pin "2") (pinfunction "2_2") (pintype "passive"))
      (node (ref "R95") (pin "2") (pinfunction "2_2") (pintype "passive"))
      (node (ref "U5") (pin "5") (pinfunction "Y5_5") (pintype "passive"))
    )
    (net (code "30") (name "/AD27") (class "Default")
      (node (ref "DZ14") (pin "1") (pintype "passive"))
      (node (ref "R127") (pin "2") (pinfunction "2_2") (pintype "passive"))
      (node (ref "R173") (pin "2") (pinfunction "2_2") (pintype "passive"))
      (node (ref "U5") (pin "1") (pinfunction "Y4_1") (pintype "passive"))
    )
    (net (code "31") (name "/AD28") (class "Default")
      (node (ref "DZ14") (pin "6") (pintype "passive"))
      (node (ref "U5") (pin "4") (pinfunction "Y7_4") (pintype "passive"))
    )
    (net (code "32") (name "/AD29") (class "Default")
      (node (ref "DZ14") (pin "3") (pintype "passive"))
      (node (ref "U5") (pin "2") (pinfunction "Y6_2") (pintype "passive"))
    )
    (net (code "33") (name "/ADC0") (class "Default")
      (node (ref "U17") (pin "3") (pinfunction "Y_3") (pintype "passive"))
    )
    (net (code "34") (name "/ADC1") (class "Default")
      (node (ref "U18") (pin "3") (pinfunction "Y_3") (pintype "passive"))
    )
    (net (code "35") (name "/ADC2") (class "Default")
      (node (ref "U20") (pin "3") (pinfunction "Y_3") (pintype "passive"))
    )
    (net (code "36") (name "/ADC3") (class "Default")
      (node (ref "U5") (pin "3") (pinfunction "Y_3") (pintype "passive"))
    )
    (net (code "37") (name "/AN-POW_1") (class "Default")
      (node (ref "D33") (pin "1") (pinfunction "A_1") (pintype "passive"))
    )
    (net (code "38") (name "/AN-POW_2") (class "Default")
      (node (ref "D21") (pin "1") (pinfunction "A_1") (pintype "passive"))
    )
    (net (code "39") (name "/CAN0-HR") (class "Default")
      (node (ref "JA1") (pin "11") (pinfunction "11_11") (pintype "passive"))
      (node (ref "R66") (pin "2") (pinfunction "2_2") (pintype "passive"))
    )
    (net (code "40") (name "/CAN0_H") (class "Default")
      (node (ref "JA1") (pin "7") (pinfunction "7_7") (pintype "passive"))
    )
    (net (code "41") (name "/CAN0_L") (class "Default")
      (node (ref "JA1") (pin "5") (pinfunction "5_5") (pintype "passive"))
      (node (ref "R66") (pin "1") (pinfunction "1_1") (pintype "passive"))
    )
    (net (code "42") (name "/CAN1-HR") (class "Default")
      (node (ref "JA1") (pin "19") (pinfunction "19_19") (pintype "passive"))
      (node (ref "R151") (pin "1") (pinfunction "1_1") (pintype "passive"))
    )
    (net (code "43") (name "/CAN1_H") (class "Default")
      (node (ref "JA1") (pin "8") (pinfunction "8_8") (pintype "passive"))
    )
    (net (code "44") (name "/CAN1_L") (class "Default")
      (node (ref "JA1") (pin "6") (pinfunction "6_6") (pintype "passive"))
      (node (ref "R151") (pin "2") (pinfunction "2_2") (pintype "passive"))
    )
    (net (code "45") (name "/CAN_SHLD0") (class "Default")
      (node (ref "JA1") (pin "9") (pinfunction "9_9") (pintype "passive"))
    )
    (net (code "46") (name "/CAN_SHLD1") (class "Default")
      (node (ref "JA1") (pin "10") (pinfunction "10_10") (pintype "passive"))
    )
    (net (code "47") (name "/DA1") (class "Default")
      (node (ref "U17") (pin "11") (pinfunction "A_11") (pintype "passive"))
    )
    (net (code "48") (name "/DA2") (class "Default")
      (node (ref "U18") (pin "11") (pinfunction "A_11") (pintype "passive"))
    )
    (net (code "49") (name "/DA3") (class "Default")
      (node (ref "U20") (pin "11") (pinfunction "A_11") (pintype "passive"))
    )
    (net (code "50") (name "/DA4") (class "Default")
      (node (ref "U5") (pin "11") (pinfunction "A_11") (pintype "passive"))
    )
    (net (code "51") (name "/DB1") (class "Default")
      (node (ref "U17") (pin "10") (pinfunction "B_10") (pintype "passive"))
    )
    (net (code "52") (name "/DB2") (class "Default")
      (node (ref "U18") (pin "10") (pinfunction "B_10") (pintype "passive"))
    )
    (net (code "53") (name "/DB3") (class "Default")
      (node (ref "U20") (pin "10") (pinfunction "B_10") (pintype "passive"))
    )
    (net (code "54") (name "/DB4") (class "Default")
      (node (ref "U5") (pin "10") (pinfunction "B_10") (pintype "passive"))
    )
    (net (code "55") (name "/DC1") (class "Default")
      (node (ref "U17") (pin "9") (pinfunction "C_9") (pintype "passive"))
    )
    (net (code "56") (name "/DC2") (class "Default")
      (node (ref "U18") (pin "9") (pinfunction "C_9") (pintype "passive"))
    )
    (net (code "57") (name "/DC3") (class "Default")
      (node (ref "U20") (pin "9") (pinfunction "C_9") (pintype "passive"))
    )
    (net (code "58") (name "/DC4") (class "Default")
      (node (ref "U5") (pin "9") (pinfunction "C_9") (pintype "passive"))
    )
    (net (code "59") (name "/EIN-AD02") (class "Default")
      (node (ref "C76") (pin "1") (pinfunction "1_1") (pintype "passive"))
      (node (ref "JA1") (pin "17") (pinfunction "17_17") (pintype "passive"))
      (node (ref "R8") (pin "2") (pinfunction "2_2") (pintype "passive"))
      (node (ref "RP25") (pin "5") (pinfunction "5_5") (pintype "passive"))
      (node (ref "RP26") (pin "4") (pinfunction "4_4") (pintype "passive"))
    )
    (net (code "60") (name "/EIN-AD03") (class "Default")
      (node (ref "C77") (pin "1") (pinfunction "1_1") (pintype "passive"))
      (node (ref "JA1") (pin "21") (pinfunction "21_21") (pintype "passive"))
      (node (ref "R19") (pin "2") (pinfunction "2_2") (pintype "passive"))
      (node (ref "RP25") (pin "6") (pinfunction "6_6") (pintype "passive"))
      (node (ref "RP26") (pin "3") (pinfunction "3_3") (pintype "passive"))
    )
    (net (code "61") (name "/EIN-AD04") (class "Default")
      (node (ref "C30") (pin "1") (pinfunction "1_1") (pintype "passive"))
      (node (ref "JA1") (pin "25") (pinfunction "25_25") (pintype "passive"))
      (node (ref "R20") (pin "2") (pinfunction "2_2") (pintype "passive"))
      (node (ref "RP25") (pin "7") (pinfunction "7_7") (pintype "passive"))
      (node (ref "RP26") (pin "2") (pinfunction "2_2") (pintype "passive"))
    )
    (net (code "62") (name "/EIN-AD05") (class "Default")
      (node (ref "C79") (pin "1") (pinfunction "1_1") (pintype "passive"))
      (node (ref "JA1") (pin "27") (pinfunction "27_27") (pintype "passive"))
      (node (ref "R30") (pin "2") (pinfunction "2_2") (pintype "passive"))
      (node (ref "RP25") (pin "8") (pinfunction "8_8") (pintype "passive"))
      (node (ref "RP26") (pin "1") (pinfunction "1_1") (pintype "passive"))
    )
    (net (code "63") (name "/EIN-ST01") (class "Default")
      (node (ref "JB1") (pin "5") (pinfunction "5_5") (pintype "passive"))
      (node (ref "R182") (pin "1") (pinfunction "1_1") (pintype "passive"))
    )
    (net (code "64") (name "/EIN-ST02") (class "Default")
      (node (ref "JB1") (pin "7") (pinfunction "7_7") (pintype "passive"))
      (node (ref "R183") (pin "1") (pinfunction "1_1") (pintype "passive"))
    )
    (net (code "65") (name "/EIN-ST03") (class "Default")
      (node (ref "JB1") (pin "9") (pinfunction "9_9") (pintype "passive"))
      (node (ref "R186") (pin "1") (pinfunction "1_1") (pintype "passive"))
    )
    (net (code "66") (name "/EIN-ST04") (class "Default")
      (node (ref "JB1") (pin "11") (pinfunction "11_11") (pintype "passive"))
      (node (ref "R187") (pin "1") (pinfunction "1_1") (pintype "passive"))
    )
    (net (code "67") (name "/EIN-ST05") (class "Default")
      (node (ref "JB1") (pin "13") (pinfunction "13_13") (pintype "passive"))
      (node (ref "R190") (pin "1") (pinfunction "1_1") (pintype "passive"))
    )
    (net (code "68") (name "/EIN-ST06") (class "Default")
      (node (ref "JB1") (pin "15") (pinfunction "15_15") (pintype "passive"))
      (node (ref "R191") (pin "1") (pinfunction "1_1") (pintype "passive"))
    )
    (net (code "69") (name "/EIN-ST07") (class "Default")
      (node (ref "JB1") (pin "17") (pinfunction "17_17") (pintype "passive"))
      (node (ref "R198") (pin "1") (pinfunction "1_1") (pintype "passive"))
    )
    (net (code "70") (name "/EIN-ST09") (class "Default")
      (node (ref "C101") (pin "2") (pinfunction "2_2") (pintype "passive"))
      (node (ref "D41") (pin "2") (pinfunction "K_2") (pintype "passive"))
      (node (ref "D42") (pin "2") (pinfunction "2_2") (pintype "passive"))
      (node (ref "JB1") (pin "20") (pinfunction "20_20") (pintype "passive"))
      (node (ref "R201") (pin "1") (pinfunction "1_1") (pintype "passive"))
    )
    (net (code "71") (name "/EIN-ST10") (class "Default")
      (node (ref "JB1") (pin "18") (pinfunction "18_18") (pintype "passive"))
      (node (ref "R203") (pin "1") (pinfunction "1_1") (pintype "passive"))
    )
    (net (code "72") (name "/EIN-ST11") (class "Default")
      (node (ref "JB1") (pin "16") (pinfunction "16_16") (pintype "passive"))
      (node (ref "R205") (pin "1") (pinfunction "1_1") (pintype "passive"))
    )
    (net (code "73") (name "/EIN-ST12") (class "Default")
      (node (ref "JB1") (pin "14") (pinfunction "14_14") (pintype "passive"))
      (node (ref "R206") (pin "1") (pinfunction "1_1") (pintype "passive"))
    )
    (net (code "74") (name "/EIN-ST13") (class "Default")
      (node (ref "JB1") (pin "12") (pinfunction "12_12") (pintype "passive"))
      (node (ref "R207") (pin "1") (pinfunction "1_1") (pintype "passive"))
    )
    (net (code "75") (name "/EIN-ST14") (class "Default")
      (node (ref "JB1") (pin "10") (pinfunction "10_10") (pintype "passive"))
      (node (ref "R208") (pin "1") (pinfunction "1_1") (pintype "passive"))
    )
    (net (code "76") (name "/EIN-ST15") (class "Default")
      (node (ref "JB1") (pin "8") (pinfunction "8_8") (pintype "passive"))
      (node (ref "R209") (pin "1") (pinfunction "1_1") (pintype "passive"))
    )
    (net (code "77") (name "/EIN-ST16") (class "Default")
      (node (ref "JB1") (pin "6") (pinfunction "6_6") (pintype "passive"))
      (node (ref "R214") (pin "1") (pinfunction "1_1") (pintype "passive"))
    )
    (net (code "78") (name "/EIN-ST17") (class "Default")
      (node (ref "JA1") (pin "28") (pinfunction "28_28") (pintype "passive"))
      (node (ref "R59") (pin "1") (pinfunction "1_1") (pintype "passive"))
    )
    (net (code "79") (name "/EIN-ST18") (class "Default")
      (node (ref "JA1") (pin "26") (pinfunction "26_26") (pintype "passive"))
      (node (ref "R60") (pin "1") (pinfunction "1_1") (pintype "passive"))
    )
    (net (code "80") (name "/EIN-ST19") (class "Default")
      (node (ref "JA1") (pin "24") (pinfunction "24_24") (pintype "passive"))
      (node (ref "R61") (pin "1") (pinfunction "1_1") (pintype "passive"))
    )
    (net (code "81") (name "/EIN-ST20") (class "Default")
      (node (ref "JA1") (pin "22") (pinfunction "22_22") (pintype "passive"))
      (node (ref "R63") (pin "1") (pinfunction "1_1") (pintype "passive"))
    )
    (net (code "82") (name "/EIN-ST21") (class "Default")
      (node (ref "JA1") (pin "20") (pinfunction "20_20") (pintype "passive"))
      (node (ref "R64") (pin "1") (pinfunction "1_1") (pintype "passive"))
    )
    (net (code "83") (name "/EIN-ST22") (class "Default")
      (node (ref "JA1") (pin "18") (pinfunction "18_18") (pintype "passive"))
      (node (ref "R65") (pin "1") (pinfunction "1_1") (pintype "passive"))
    )
    (net (code "84") (name "/EIN-ST23") (class "Default")
      (node (ref "JA1") (pin "16") (pinfunction "16_16") (pintype "passive"))
      (node (ref "R68") (pin "1") (pinfunction "1_1") (pintype "passive"))
    )
    (net (code "85") (name "/EIN-ST24") (class "Default")
      (node (ref "JA1") (pin "14") (pinfunction "14_14") (pintype "passive"))
      (node (ref "R69") (pin "1") (pinfunction "1_1") (pintype "passive"))
    )
    (net (code "86") (name "/EIN-ST25") (class "Default")
      (node (ref "JA1") (pin "15") (pinfunction "15_15") (pintype "passive"))
      (node (ref "R85") (pin "1") (pinfunction "1_1") (pintype "passive"))
    )
    (net (code "87") (name "/EIN-ST27") (class "Default")
      (node (ref "JB1") (pin "19") (pinfunction "19_19") (pintype "passive"))
      (node (ref "R111") (pin "1") (pinfunction "1_1") (pintype "passive"))
    )
    (net (code "88") (name "/F02") (class "Default")
      (node (ref "D37") (pin "2") (pinfunction "K_2") (pintype "passive"))
      (node (ref "DZ13") (pin "3") (pintype "passive"))
      (node (ref "RP25") (pin "4") (pinfunction "4_4") (pintype "passive"))
      (node (ref "U5") (pin "12") (pinfunction "Y3_12") (pintype "passive"))
    )
    (net (code "89") (name "/F03") (class "Default")
      (node (ref "D18") (pin "2") (pinfunction "K_2") (pintype "passive"))
      (node (ref "DZ13") (pin "1") (pintype "passive"))
      (node (ref "RP25") (pin "3") (pinfunction "3_3") (pintype "passive"))
      (node (ref "U5") (pin "13") (pinfunction "Y0_13") (pintype "passive"))
    )
    (net (code "90") (name "/F04") (class "Default")
      (node (ref "D20") (pin "2") (pinfunction "K_2") (pintype "passive"))
      (node (ref "DZ13") (pin "6") (pintype "passive"))
      (node (ref "RP25") (pin "2") (pinfunction "2_2") (pintype "passive"))
      (node (ref "U5") (pin "14") (pinfunction "Y1_14") (pintype "passive"))
    )
    (net (code "91") (name "/F05") (class "Default")
      (node (ref "D23") (pin "2") (pinfunction "K_2") (pintype "passive"))
      (node (ref "DZ13") (pin "4") (pintype "passive"))
      (node (ref "RP25") (pin "1") (pinfunction "1_1") (pintype "passive"))
      (node (ref "U5") (pin "15") (pinfunction "Y2_15") (pintype "passive"))
    )
    (net (code "92") (name "/F49") (class "Default")
      (node (ref "JB1") (pin "1") (pinfunction "1_1") (pintype "passive"))
    )
    (net (code "93") (name "/F50") (class "Default")
      (node (ref "JB1") (pin "2") (pinfunction "2_2") (pintype "passive"))
    )
    (net (code "94") (name "/OUT1") (class "Default")
      (node (ref "JA1") (pin "1") (pinfunction "1_1") (pintype "passive"))
    )
    (net (code "95") (name "/OUT2") (class "Default")
      (node (ref "JA1") (pin "2") (pinfunction "2_2") (pintype "passive"))
    )
    (net (code "96") (name "/PWMOUT1") (class "Default")
      (node (ref "JA1") (pin "23") (pinfunction "23_23") (pintype "passive"))
    )
    (net (code "97") (name "/PWMOUT2") (class "Default")
      (node (ref "JA1") (pin "13") (pinfunction "13_13") (pintype "passive"))
    )
    (net (code "98") (name "/V-POW") (class "Default")
      (node (ref "D12") (pin "1") (pinfunction "A_1") (pintype "passive"))
    )
    (net (code "99") (name "GND") (class "Default")
      (node (ref "C1") (pin "2") (pinfunction "2_2") (pintype "passive"))
      (node (ref "C101") (pin "1") (pinfunction "1_1") (pintype "passive"))
      (node (ref "C26") (pin "2") (pinfunction "2_2") (pintype "passive"))
      (node (ref "C27") (pin "2") (pinfunction "2_2") (pintype "passive"))
      (node (ref "C28") (pin "2") (pinfunction "2_2") (pintype "passive"))
      (node (ref "C29") (pin "2") (pinfunction "2_2") (pintype "passive"))
      (node (ref "C30") (pin "2") (pinfunction "2_2") (pintype "passive"))
      (node (ref "C31") (pin "2") (pinfunction "2_2") (pintype "passive"))
      (node (ref "C33") (pin "2") (pinfunction "2_2") (pintype "passive"))
      (node (ref "C40") (pin "2") (pinfunction "2_2") (pintype "passive"))
      (node (ref "C41") (pin "2") (pinfunction "2_2") (pintype "passive"))
      (node (ref "C42") (pin "2") (pinfunction "2_2") (pintype "passive"))
      (node (ref "C43") (pin "2") (pinfunction "2_2") (pintype "passive"))
      (node (ref "C44") (pin "2") (pinfunction "2_2") (pintype "passive"))
      (node (ref "C45") (pin "2") (pinfunction "2_2") (pintype "passive"))
      (node (ref "C46") (pin "2") (pinfunction "2_2") (pintype "passive"))
      (node (ref "C47") (pin "2") (pinfunction "2_2") (pintype "passive"))
      (node (ref "C58") (pin "2") (pinfunction "2_2") (pintype "passive"))
      (node (ref "C59") (pin "2") (pinfunction "2_2") (pintype "passive"))
      (node (ref "C60") (pin "2") (pinfunction "2_2") (pintype "passive"))
      (node (ref "C61") (pin "2") (pinfunction "2_2") (pintype "passive"))
      (node (ref "C62") (pin "2") (pinfunction "2_2") (pintype "passive"))
      (node (ref "C63") (pin "2") (pinfunction "2_2") (pintype "passive"))
      (node (ref "C64") (pin "2") (pinfunction "2_2") (pintype "passive"))
      (node (ref "C65") (pin "2") (pinfunction "2_2") (pintype "passive"))
      (node (ref "C67") (pin "1") (pinfunction "1_1") (pintype "passive"))
      (node (ref "C68") (pin "2") (pinfunction "2_2") (pintype "passive"))
      (node (ref "C69") (pin "1") (pinfunction "1_1") (pintype "passive"))
      (node (ref "C70") (pin "1") (pinfunction "1_1") (pintype "passive"))
      (node (ref "C71") (pin "1") (pinfunction "1_1") (pintype "passive"))
      (node (ref "C72") (pin "1") (pinfunction "1_1") (pintype "passive"))
      (node (ref "C73") (pin "1") (pinfunction "1_1") (pintype "passive"))
      (node (ref "C74") (pin "2") (pinfunction "2_2") (pintype "passive"))
      (node (ref "C76") (pin "2") (pinfunction "2_2") (pintype "passive"))
      (node (ref "C77") (pin "2") (pinfunction "2_2") (pintype "passive"))
      (node (ref "C79") (pin "2") (pinfunction "2_2") (pintype "passive"))
      (node (ref "C85") (pin "2") (pinfunction "2_2") (pintype "passive"))
      (node (ref "C91") (pin "2") (pinfunction "2_2") (pintype "passive"))
      (node (ref "C92") (pin "2") (pinfunction "2_2") (pintype "passive"))
      (node (ref "D18") (pin "1") (pinfunction "A_1") (pintype "passive"))
      (node (ref "D20") (pin "1") (pinfunction "A_1") (pintype "passive"))
      (node (ref "D23") (pin "1") (pinfunction "A_1") (pintype "passive"))
      (node (ref "D37") (pin "1") (pinfunction "A_1") (pintype "passive"))
      (node (ref "D41") (pin "1") (pinfunction "A_1") (pintype "passive"))
      (node (ref "D42") (pin "1") (pinfunction "1_1") (pintype "passive"))
      (node (ref "DZ10") (pin "2") (pintype "passive"))
      (node (ref "DZ11") (pin "2") (pintype "passive"))
      (node (ref "DZ13") (pin "2") (pintype "passive"))
      (node (ref "DZ14") (pin "2") (pintype "passive"))
      (node (ref "DZ4") (pin "2") (pintype "passive"))
      (node (ref "DZ5") (pin "2") (pintype "passive"))
      (node (ref "DZ7") (pin "2") (pintype "passive"))
      (node (ref "DZ8") (pin "2") (pintype "passive"))
      (node (ref "JA1") (pin "12") (pinfunction "12_12") (pintype "passive"))
      (node (ref "JB1") (pin "4") (pinfunction "4_4") (pintype "passive"))
      (node (ref "Q13") (pin "2") (pinfunction "gnd_2") (pintype "passive"))
      (node (ref "Q16") (pin "2") (pinfunction "gnd_2") (pintype "passive"))
      (node (ref "Q2") (pin "2") (pinfunction "gnd_2") (pintype "passive"))
      (node (ref "R173") (pin "1") (pinfunction "1_1") (pintype "passive"))
      (node (ref "R87") (pin "2") (pinfunction "2_2") (pintype "passive"))
      (node (ref "R88") (pin "2") (pinfunction "2_2") (pintype "passive"))
      (node (ref "R89") (pin "2") (pinfunction "2_2") (pintype "passive"))
      (node (ref "R90") (pin "2") (pinfunction "2_2") (pintype "passive"))
      (node (ref "R95") (pin "1") (pinfunction "1_1") (pintype "passive"))
      (node (ref "RP10") (pin "1") (pinfunction "1_1") (pintype "passive"))
      (node (ref "RP10") (pin "2") (pinfunction "2_2") (pintype "passive"))
      (node (ref "RP10") (pin "3") (pinfunction "3_3") (pintype "passive"))
      (node (ref "RP10") (pin "4") (pinfunction "4_4") (pintype "passive"))
      (node (ref "RP18") (pin "1") (pinfunction "1_1") (pintype "passive"))
      (node (ref "RP18") (pin "2") (pinfunction "2_2") (pintype "passive"))
      (node (ref "RP18") (pin "3") (pinfunction "3_3") (pintype "passive"))
      (node (ref "RP18") (pin "4") (pinfunction "4_4") (pintype "passive"))
      (node (ref "RP23") (pin "1") (pinfunction "1_1") (pintype "passive"))
      (node (ref "RP23") (pin "2") (pinfunction "2_2") (pintype "passive"))
      (node (ref "RP23") (pin "3") (pinfunction "3_3") (pintype "passive"))
      (node (ref "RP23") (pin "4") (pinfunction "4_4") (pintype "passive"))
      (node (ref "RP24") (pin "1") (pinfunction "1_1") (pintype "passive"))
      (node (ref "RP24") (pin "2") (pinfunction "2_2") (pintype "passive"))
      (node (ref "RP24") (pin "3") (pinfunction "3_3") (pintype "passive"))
      (node (ref "RP24") (pin "4") (pinfunction "4_4") (pintype "passive"))
      (node (ref "RP26") (pin "5") (pinfunction "5_5") (pintype "passive"))
      (node (ref "RP26") (pin "6") (pinfunction "6_6") (pintype "passive"))
      (node (ref "RP26") (pin "7") (pinfunction "7_7") (pintype "passive"))
      (node (ref "RP26") (pin "8") (pinfunction "8_8") (pintype "passive"))
      (node (ref "RP5") (pin "1") (pinfunction "1_1") (pintype "passive"))
      (node (ref "RP5") (pin "2") (pinfunction "2_2") (pintype "passive"))
      (node (ref "RP5") (pin "3") (pinfunction "3_3") (pintype "passive"))
      (node (ref "RP5") (pin "4") (pinfunction "4_4") (pintype "passive"))
      (node (ref "RP9") (pin "1") (pinfunction "1_1") (pintype "passive"))
      (node (ref "RP9") (pin "2") (pinfunction "2_2") (pintype "passive"))
      (node (ref "RP9") (pin "3") (pinfunction "3_3") (pintype "passive"))
      (node (ref "RP9") (pin "4") (pinfunction "4_4") (pintype "passive"))
      (node (ref "U17") (pin "7") (pinfunction "VEE_7") (pintype "passive"))
      (node (ref "U17") (pin "8") (pinfunction "GND_8") (pintype "passive"))
      (node (ref "U18") (pin "7") (pinfunction "VEE_7") (pintype "passive"))
      (node (ref "U18") (pin "8") (pinfunction "GND_8") (pintype "passive"))
      (node (ref "U20") (pin "7") (pinfunction "VEE_7") (pintype "passive"))
      (node (ref "U20") (pin "8") (pinfunction "GND_8") (pintype "passive"))
      (node (ref "U5") (pin "7") (pinfunction "VEE_7") (pintype "passive"))
      (node (ref "U5") (pin "8") (pinfunction "GND_8") (pintype "passive"))
    )
    (net (code "100") (name "Net-(C26-Pad1)") (class "Default")
      (node (ref "C26") (pin "1") (pinfunction "1_1") (pintype "passive"))
      (node (ref "R182") (pin "2") (pinfunction "2_2") (pintype "passive"))
      (node (ref "R44") (pin "1") (pinfunction "1_1") (pintype "passive"))
      (node (ref "RP6") (pin "1") (pinfunction "1_1") (pintype "passive"))
    )
    (net (code "101") (name "Net-(C27-Pad1)") (class "Default")
      (node (ref "C27") (pin "1") (pinfunction "1_1") (pintype "passive"))
      (node (ref "R183") (pin "2") (pinfunction "2_2") (pintype "passive"))
      (node (ref "R71") (pin "1") (pinfunction "1_1") (pintype "passive"))
      (node (ref "RP6") (pin "2") (pinfunction "2_2") (pintype "passive"))
    )
    (net (code "102") (name "Net-(C28-Pad1)") (class "Default")
      (node (ref "C28") (pin "1") (pinfunction "1_1") (pintype "passive"))
      (node (ref "R186") (pin "2") (pinfunction "2_2") (pintype "passive"))
      (node (ref "R91") (pin "1") (pinfunction "1_1") (pintype "passive"))
      (node (ref "RP6") (pin "3") (pinfunction "3_3") (pintype "passive"))
    )
    (net (code "103") (name "Net-(C29-Pad1)") (class "Default")
      (node (ref "C29") (pin "1") (pinfunction "1_1") (pintype "passive"))
      (node (ref "R187") (pin "2") (pinfunction "2_2") (pintype "passive"))
      (node (ref "R92") (pin "1") (pinfunction "1_1") (pintype "passive"))
      (node (ref "RP6") (pin "4") (pinfunction "4_4") (pintype "passive"))
    )
    (net (code "104") (name "Net-(C31-Pad1)") (class "Default")
      (node (ref "C31") (pin "1") (pinfunction "1_1") (pintype "passive"))
      (node (ref "R166") (pin "1") (pinfunction "1_1") (pintype "passive"))
      (node (ref "R191") (pin "2") (pinfunction "2_2") (pintype "passive"))
      (node (ref "RP8") (pin "2") (pinfunction "2_2") (pintype "passive"))
    )
    (net (code "105") (name "Net-(C33-Pad1)") (class "Default")
      (node (ref "C33") (pin "1") (pinfunction "1_1") (pintype "passive"))
      (node (ref "R113") (pin "1") (pinfunction "1_1") (pintype "passive"))
      (node (ref "R199") (pin "2") (pinfunction "2_2") (pintype "passive"))
      (node (ref "RP8") (pin "4") (pinfunction "4_4") (pintype "passive"))
    )
    (net (code "106") (name "Net-(C40-Pad1)") (class "Default")
      (node (ref "C40") (pin "1") (pinfunction "1_1") (pintype "passive"))
      (node (ref "R119") (pin "1") (pinfunction "1_1") (pintype "passive"))
      (node (ref "R206") (pin "2") (pinfunction "2_2") (pintype "passive"))
      (node (ref "RP15") (pin "4") (pinfunction "4_4") (pintype "passive"))
    )
    (net (code "107") (name "Net-(C41-Pad1)") (class "Default")
      (node (ref "C41") (pin "1") (pinfunction "1_1") (pintype "passive"))
      (node (ref "R120") (pin "1") (pinfunction "1_1") (pintype "passive"))
      (node (ref "R205") (pin "2") (pinfunction "2_2") (pintype "passive"))
      (node (ref "RP15") (pin "3") (pinfunction "3_3") (pintype "passive"))
    )
    (net (code "108") (name "Net-(C42-Pad1)") (class "Default")
      (node (ref "C42") (pin "1") (pinfunction "1_1") (pintype "passive"))
      (node (ref "R121") (pin "1") (pinfunction "1_1") (pintype "passive"))
      (node (ref "R203") (pin "2") (pinfunction "2_2") (pintype "passive"))
      (node (ref "RP15") (pin "2") (pinfunction "2_2") (pintype "passive"))
    )
    (net (code "109") (name "Net-(C43-Pad1)") (class "Default")
      (node (ref "C43") (pin "1") (pinfunction "1_1") (pintype "passive"))
      (node (ref "R122") (pin "1") (pinfunction "1_1") (pintype "passive"))
      (node (ref "R201") (pin "2") (pinfunction "2_2") (pintype "passive"))
      (node (ref "RP15") (pin "1") (pinfunction "1_1") (pintype "passive"))
    )
    (net (code "110") (name "Net-(C44-Pad1)") (class "Default")
      (node (ref "C44") (pin "1") (pinfunction "1_1") (pintype "passive"))
      (node (ref "R123") (pin "1") (pinfunction "1_1") (pintype "passive"))
      (node (ref "R214") (pin "2") (pinfunction "2_2") (pintype "passive"))
      (node (ref "RP17") (pin "4") (pinfunction "4_4") (pintype "passive"))
    )
    (net (code "111") (name "Net-(C45-Pad1)") (class "Default")
      (node (ref "C45") (pin "1") (pinfunction "1_1") (pintype "passive"))
      (node (ref "R124") (pin "1") (pinfunction "1_1") (pintype "passive"))
      (node (ref "R209") (pin "2") (pinfunction "2_2") (pintype "passive"))
      (node (ref "RP17") (pin "3") (pinfunction "3_3") (pintype "passive"))
    )
    (net (code "112") (name "Net-(C46-Pad1)") (class "Default")
      (node (ref "C46") (pin "1") (pinfunction "1_1") (pintype "passive"))
      (node (ref "R125") (pin "1") (pinfunction "1_1") (pintype "passive"))
      (node (ref "R208") (pin "2") (pinfunction "2_2") (pintype "passive"))
      (node (ref "RP17") (pin "2") (pinfunction "2_2") (pintype "passive"))
    )
    (net (code "113") (name "Net-(C47-Pad1)") (class "Default")
      (node (ref "C47") (pin "1") (pinfunction "1_1") (pintype "passive"))
      (node (ref "R126") (pin "1") (pinfunction "1_1") (pintype "passive"))
      (node (ref "R207") (pin "2") (pinfunction "2_2") (pintype "passive"))
      (node (ref "RP17") (pin "1") (pinfunction "1_1") (pintype "passive"))
    )
    (net (code "114") (name "Net-(C58-Pad1)") (class "Default")
      (node (ref "C58") (pin "1") (pinfunction "1_1") (pintype "passive"))
      (node (ref "R168") (pin "1") (pinfunction "1_1") (pintype "passive"))
      (node (ref "R63") (pin "2") (pinfunction "2_2") (pintype "passive"))
      (node (ref "RP21") (pin "5") (pinfunction "5_5") (pintype "passive"))
    )
    (net (code "115") (name "Net-(C59-Pad1)") (class "Default")
      (node (ref "C59") (pin "1") (pinfunction "1_1") (pintype "passive"))
      (node (ref "R61") (pin "2") (pinfunction "2_2") (pintype "passive"))
      (node (ref "R72") (pin "1") (pinfunction "1_1") (pintype "passive"))
      (node (ref "RP21") (pin "6") (pinfunction "6_6") (pintype "passive"))
    )
    (net (code "116") (name "Net-(C60-Pad1)") (class "Default")
      (node (ref "C60") (pin "1") (pinfunction "1_1") (pintype "passive"))
      (node (ref "R60") (pin "2") (pinfunction "2_2") (pintype "passive"))
      (node (ref "R77") (pin "1") (pinfunction "1_1") (pintype "passive"))
      (node (ref "RP21") (pin "7") (pinfunction "7_7") (pintype "passive"))
    )
    (net (code "117") (name "Net-(C61-Pad1)") (class "Default")
      (node (ref "C61") (pin "1") (pinfunction "1_1") (pintype "passive"))
      (node (ref "R59") (pin "2") (pinfunction "2_2") (pintype "passive"))
      (node (ref "R82") (pin "1") (pinfunction "1_1") (pintype "passive"))
      (node (ref "RP21") (pin "8") (pinfunction "8_8") (pintype "passive"))
    )
    (net (code "118") (name "Net-(C62-Pad1)") (class "Default")
      (node (ref "C62") (pin "1") (pinfunction "1_1") (pintype "passive"))
      (node (ref "R49") (pin "1") (pinfunction "1_1") (pintype "passive"))
      (node (ref "R69") (pin "2") (pinfunction "2_2") (pintype "passive"))
      (node (ref "RP22") (pin "5") (pinfunction "5_5") (pintype "passive"))
    )
    (net (code "119") (name "Net-(C63-Pad1)") (class "Default")
      (node (ref "C63") (pin "1") (pinfunction "1_1") (pintype "passive"))
      (node (ref "R108") (pin "1") (pinfunction "1_1") (pintype "passive"))
      (node (ref "R68") (pin "2") (pinfunction "2_2") (pintype "passive"))
      (node (ref "RP22") (pin "6") (pinfunction "6_6") (pintype "passive"))
    )
    (net (code "120") (name "Net-(C64-Pad1)") (class "Default")
      (node (ref "C64") (pin "1") (pinfunction "1_1") (pintype "passive"))
      (node (ref "R51") (pin "1") (pinfunction "1_1") (pintype "passive"))
      (node (ref "R65") (pin "2") (pinfunction "2_2") (pintype "passive"))
      (node (ref "RP22") (pin "7") (pinfunction "7_7") (pintype "passive"))
    )
    (net (code "121") (name "Net-(C65-Pad1)") (class "Default")
      (node (ref "C65") (pin "1") (pinfunction "1_1") (pintype "passive"))
      (node (ref "R52") (pin "1") (pinfunction "1_1") (pintype "passive"))
      (node (ref "R64") (pin "2") (pinfunction "2_2") (pintype "passive"))
      (node (ref "RP22") (pin "8") (pinfunction "8_8") (pintype "passive"))
    )
    (net (code "122") (name "Net-(C68-Pad1)") (class "Default")
      (node (ref "C68") (pin "1") (pinfunction "1_1") (pintype "passive"))
      (node (ref "R80") (pin "1") (pinfunction "1_1") (pintype "passive"))
      (node (ref "R83") (pin "1") (pinfunction "1_1") (pintype "passive"))
      (node (ref "R85") (pin "2") (pinfunction "2_2") (pintype "passive"))
    )
    (net (code "123") (name "Net-(C85-Pad1)") (class "Default")
      (node (ref "C85") (pin "1") (pinfunction "1_1") (pintype "passive"))
      (node (ref "R109") (pin "1") (pinfunction "1_1") (pintype "passive"))
      (node (ref "R111") (pin "2") (pinfunction "2_2") (pintype "passive"))
      (node (ref "R127") (pin "1") (pinfunction "1_1") (pintype "passive"))
    )
    (net (code "124") (name "Net-(C91-Pad1)") (class "Default")
      (node (ref "C91") (pin "1") (pinfunction "1_1") (pintype "passive"))
      (node (ref "R190") (pin "2") (pinfunction "2_2") (pintype "passive"))
      (node (ref "R94") (pin "1") (pinfunction "1_1") (pintype "passive"))
      (node (ref "RP8") (pin "1") (pinfunction "1_1") (pintype "passive"))
    )
    (net (code "125") (name "Net-(C92-Pad1)") (class "Default")
      (node (ref "C92") (pin "1") (pinfunction "1_1") (pintype "passive"))
      (node (ref "R112") (pin "1") (pinfunction "1_1") (pintype "passive"))
      (node (ref "R198") (pin "2") (pinfunction "2_2") (pintype "passive"))
      (node (ref "RP8") (pin "3") (pinfunction "3_3") (pintype "passive"))
    )
    (net (code "126") (name "Net-(D4-A)") (class "Default")
      (node (ref "D4") (pin "1") (pinfunction "A_1") (pintype "passive"))
      (node (ref "Q14") (pin "2") (pinfunction "C_2") (pintype "passive"))
      (node (ref "R86") (pin "2") (pinfunction "2_2") (pintype "passive"))
    )
    (net (code "127") (name "Net-(D4-K)") (class "Default")
      (node (ref "C73") (pin "2") (pinfunction "2_2") (pintype "passive"))
      (node (ref "D4") (pin "2") (pinfunction "K_2") (pintype "passive"))
      (node (ref "R19") (pin "1") (pinfunction "1_1") (pintype "passive"))
      (node (ref "R8") (pin "1") (pinfunction "1_1") (pintype "passive"))
    )
    (net (code "128") (name "Net-(D12-K)") (class "Default")
      (node (ref "D12") (pin "2") (pinfunction "K_2") (pintype "passive"))
      (node (ref "Q2") (pin "1") (pinfunction "in_1") (pintype "input"))
    )
    (net (code "129") (name "Net-(D17-A)") (class "Default")
      (node (ref "D17") (pin "1") (pinfunction "A_1") (pintype "passive"))
      (node (ref "D28") (pin "1") (pinfunction "A_1") (pintype "passive"))
      (node (ref "Q17") (pin "2") (pinfunction "C_2") (pintype "passive"))
      (node (ref "R132") (pin "2") (pinfunction "2_2") (pintype "passive"))
    )
    (net (code "130") (name "Net-(D17-K)") (class "Default")
      (node (ref "C74") (pin "1") (pinfunction "1_1") (pintype "passive"))
      (node (ref "D17") (pin "2") (pinfunction "K_2") (pintype "passive"))
      (node (ref "R30") (pin "1") (pinfunction "1_1") (pintype "passive"))
    )
    (net (code "131") (name "Net-(D21-K)") (class "Default")
      (node (ref "D21") (pin "2") (pinfunction "K_2") (pintype "passive"))
      (node (ref "Q16") (pin "1") (pinfunction "in_1") (pintype "input"))
    )
    (net (code "132") (name "Net-(D28-K)") (class "Default")
      (node (ref "C67") (pin "2") (pinfunction "2_2") (pintype "passive"))
      (node (ref "D28") (pin "2") (pinfunction "K_2") (pintype "passive"))
      (node (ref "R20") (pin "1") (pinfunction "1_1") (pintype "passive"))
    )
    (net (code "133") (name "Net-(D33-K)") (class "Default")
      (node (ref "D33") (pin "2") (pinfunction "K_2") (pintype "passive"))
      (node (ref "Q13") (pin "1") (pinfunction "in_1") (pintype "input"))
    )
    (net (code "134") (name "Net-(Q2-out)") (class "Default")
      (node (ref "Q2") (pin "3") (pinfunction "out_3") (pintype "passive"))
      (node (ref "R16") (pin "1") (pinfunction "1_1") (pintype "passive"))
    )
    (net (code "135") (name "Net-(Q13-out)") (class "Default")
      (node (ref "Q13") (pin "3") (pinfunction "out_3") (pintype "passive"))
      (node (ref "R84") (pin "2") (pinfunction "2_2") (pintype "passive"))
    )
    (net (code "136") (name "Net-(Q14-B)") (class "Default")
      (node (ref "Q14") (pin "1") (pinfunction "B_1") (pintype "input"))
      (node (ref "R81") (pin "2") (pinfunction "2_2") (pintype "passive"))
      (node (ref "R84") (pin "1") (pinfunction "1_1") (pintype "passive"))
    )
    (net (code "137") (name "Net-(Q16-out)") (class "Default")
      (node (ref "Q16") (pin "3") (pinfunction "out_3") (pintype "passive"))
      (node (ref "R128") (pin "1") (pinfunction "1_1") (pintype "passive"))
    )
    (net (code "138") (name "Net-(Q17-B)") (class "Default")
      (node (ref "Q17") (pin "1") (pinfunction "B_1") (pintype "input"))
      (node (ref "R128") (pin "2") (pinfunction "2_2") (pintype "passive"))
      (node (ref "R57") (pin "2") (pinfunction "2_2") (pintype "passive"))
    )
    (net (code "139") (name "Net-(Q39-B)") (class "Default")
      (node (ref "Q39") (pin "1") (pinfunction "B_1") (pintype "input"))
      (node (ref "R110") (pin "1") (pinfunction "1_1") (pintype "passive"))
      (node (ref "R16") (pin "2") (pinfunction "2_2") (pintype "passive"))
    )
    (net (code "140") (name "Net-(U5-~{E})") (class "Default")
      (node (ref "R87") (pin "1") (pinfunction "1_1") (pintype "passive"))
      (node (ref "U5") (pin "6") (pinfunction "~{E}_6") (pintype "passive"))
    )
    (net (code "141") (name "Net-(U17-~{E})") (class "Default")
      (node (ref "R88") (pin "1") (pinfunction "1_1") (pintype "passive"))
      (node (ref "U17") (pin "6") (pinfunction "~{E}_6") (pintype "passive"))
    )
    (net (code "142") (name "Net-(U18-~{E})") (class "Default")
      (node (ref "R89") (pin "1") (pinfunction "1_1") (pintype "passive"))
      (node (ref "U18") (pin "6") (pinfunction "~{E}_6") (pintype "passive"))
    )
    (net (code "143") (name "Net-(U20-~{E})") (class "Default")
      (node (ref "R90") (pin "1") (pinfunction "1_1") (pintype "passive"))
      (node (ref "U20") (pin "6") (pinfunction "~{E}_6") (pintype "passive"))
    )
    (net (code "144") (name "V") (class "Default")
      (node (ref "Q39") (pin "3") (pinfunction "C_3") (pintype "passive"))
      (node (ref "R110") (pin "2") (pinfunction "2_2") (pintype "passive"))
      (node (ref "R123") (pin "2") (pinfunction "2_2") (pintype "passive"))
      (node (ref "R124") (pin "2") (pinfunction "2_2") (pintype "passive"))
      (node (ref "R199") (pin "1") (pinfunction "1_1") (pintype "passive"))
      (node (ref "R2") (pin "1") (pinfunction "1_1") (pintype "passive"))
      (node (ref "R44") (pin "2") (pinfunction "2_2") (pintype "passive"))
      (node (ref "R71") (pin "2") (pinfunction "2_2") (pintype "passive"))
    )
    (net (code "145") (name "V1") (class "Default")
      (node (ref "C1") (pin "1") (pinfunction "1_1") (pintype "passive"))
      (node (ref "Q39") (pin "2") (pinfunction "E_2") (pintype "passive"))
      (node (ref "R108") (pin "2") (pinfunction "2_2") (pintype "passive"))
      (node (ref "R109") (pin "2") (pinfunction "2_2") (pintype "passive"))
      (node (ref "R112") (pin "2") (pinfunction "2_2") (pintype "passive"))
      (node (ref "R113") (pin "2") (pinfunction "2_2") (pintype "passive"))
      (node (ref "R119") (pin "2") (pinfunction "2_2") (pintype "passive"))
      (node (ref "R120") (pin "2") (pinfunction "2_2") (pintype "passive"))
      (node (ref "R121") (pin "2") (pinfunction "2_2") (pintype "passive"))
      (node (ref "R122") (pin "2") (pinfunction "2_2") (pintype "passive"))
      (node (ref "R125") (pin "2") (pinfunction "2_2") (pintype "passive"))
      (node (ref "R126") (pin "2") (pinfunction "2_2") (pintype "passive"))
      (node (ref "R166") (pin "2") (pinfunction "2_2") (pintype "passive"))
      (node (ref "R168") (pin "2") (pinfunction "2_2") (pintype "passive"))
      (node (ref "R2") (pin "2") (pinfunction "2_2") (pintype "passive"))
      (node (ref "R49") (pin "2") (pinfunction "2_2") (pintype "passive"))
      (node (ref "R51") (pin "2") (pinfunction "2_2") (pintype "passive"))
      (node (ref "R52") (pin "2") (pinfunction "2_2") (pintype "passive"))
      (node (ref "R72") (pin "2") (pinfunction "2_2") (pintype "passive"))
      (node (ref "R77") (pin "2") (pinfunction "2_2") (pintype "passive"))
      (node (ref "R80") (pin "2") (pinfunction "2_2") (pintype "passive"))
      (node (ref "R82") (pin "2") (pinfunction "2_2") (pintype "passive"))
      (node (ref "R91") (pin "2") (pinfunction "2_2") (pintype "passive"))
      (node (ref "R92") (pin "2") (pinfunction "2_2") (pintype "passive"))
      (node (ref "R94") (pin "2") (pinfunction "2_2") (pintype "passive"))
    )
    (net (code "146") (name "unconnected-(DZ4-Pad5)") (class "Default")
      (node (ref "DZ4") (pin "5") (pintype "passive+no_connect"))
    )
    (net (code "147") (name "unconnected-(DZ5-Pad5)") (class "Default")
      (node (ref "DZ5") (pin "5") (pintype "passive+no_connect"))
    )
    (net (code "148") (name "unconnected-(DZ7-Pad5)") (class "Default")
      (node (ref "DZ7") (pin "5") (pintype "passive"))
    )
    (net (code "149") (name "unconnected-(DZ8-Pad5)") (class "Default")
      (node (ref "DZ8") (pin "5") (pintype "passive"))
    )
    (net (code "150") (name "unconnected-(DZ10-Pad5)") (class "Default")
      (node (ref "DZ10") (pin "5") (pintype "passive"))
    )
    (net (code "151") (name "unconnected-(DZ11-Pad5)") (class "Default")
      (node (ref "DZ11") (pin "5") (pintype "passive"))
    )
    (net (code "152") (name "unconnected-(DZ13-Pad5)") (class "Default")
      (node (ref "DZ13") (pin "5") (pintype "passive"))
    )
    (net (code "153") (name "unconnected-(DZ14-Pad5)") (class "Default")
      (node (ref "DZ14") (pin "5") (pintype "passive"))
    )
  )
)
